# 1-Schematic_New_Project.net
KiCad netlist of a schematic drawn in EasyEDA
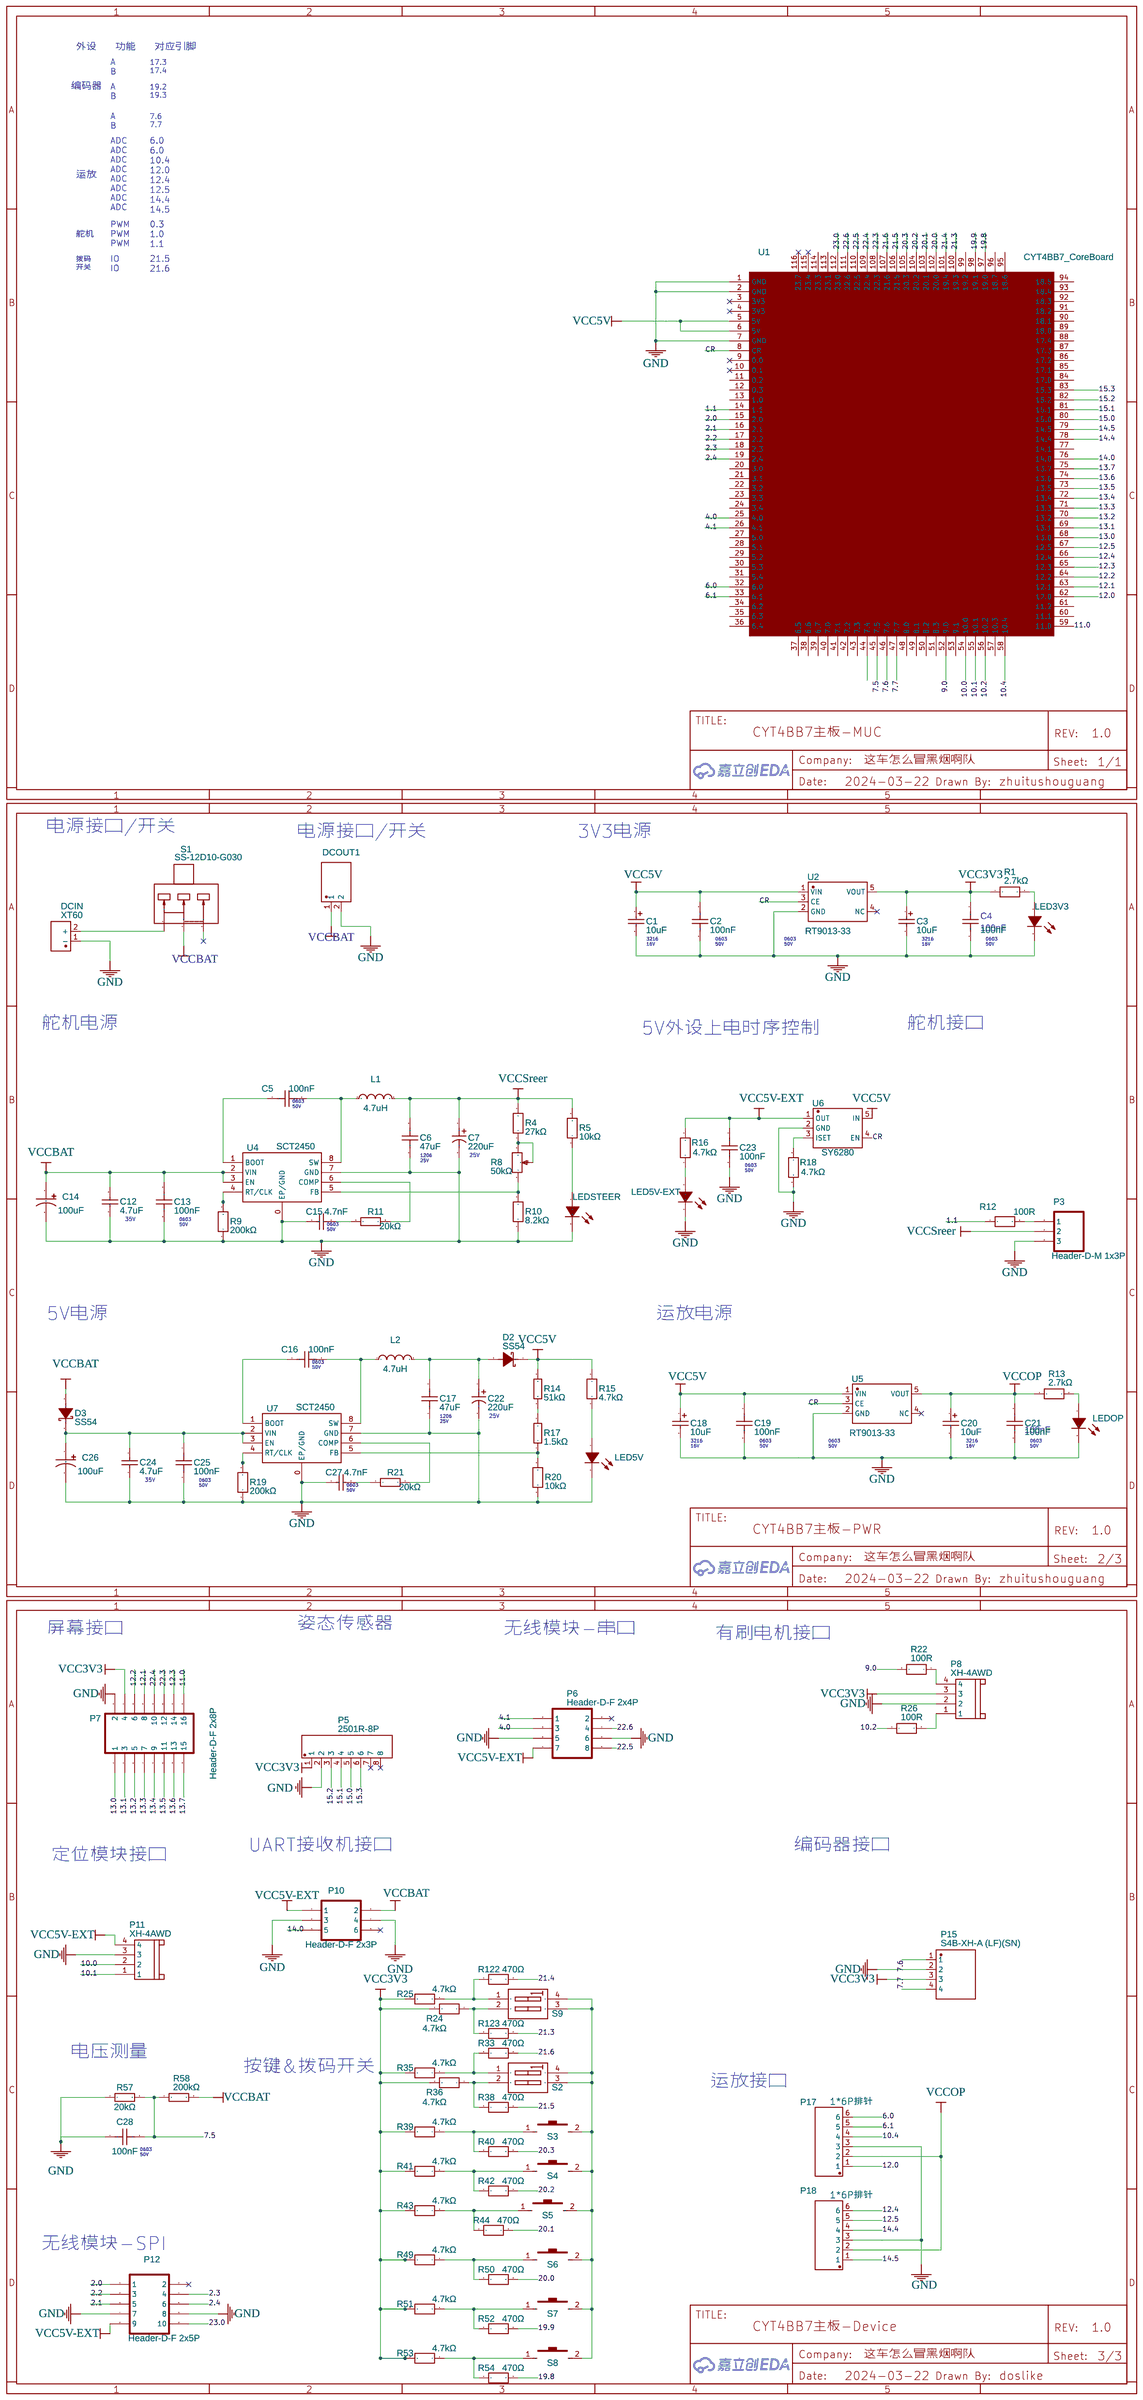
[diagram p0: schematic sheet]

(export (version "E")
  (design (tool "Eeschema 10.0.6"))
  (components
    (comp (ref "C1")
      (value "10uF")
      (fields
        (field (name "Manufacturer Part") "CA45A-A-16V-10uF-K")
        (field (name "Manufacturer") "CEC(振华新云)")
      )
      (libsource (lib "") (part "CA45A-A-16V-10UF-K"))
    )
    (comp (ref "C2")
      (value "100nF")
      (fields (field (name "Manufacturer Part") "100nF/0603/50V"))
      (libsource (lib "") (part "100NF/0603/50V"))
    )
    (comp (ref "C3")
      (value "10uF")
      (fields
        (field (name "Manufacturer Part") "CA45A-A-16V-10uF-K")
        (field (name "Manufacturer") "CEC(振华新云)")
      )
      (libsource (lib "") (part "CA45A-A-16V-10UF-K"))
    )
    (comp (ref "C4")
      (value "100nF")
      (fields (field (name "Manufacturer Part") "100nF/0603/50V"))
      (libsource (lib "") (part "100NF/0603/50V"))
    )
    (comp (ref "C5")
      (value "100nF")
      (fields (field (name "Manufacturer Part") "100nF/0603/50V"))
      (libsource (lib "") (part "100NF/0603/50V_1"))
    )
    (comp (ref "C6")
      (value "47uF")
      (fields (field (name "Manufacturer Part") "47uF, 25V,10%-1206"))
      (libsource (lib "") (part "47UF, 25V,10%-1206"))
    )
    (comp (ref "C7")
      (value "220uF")
      (fields
        (field (name "Manufacturer Part") "KNE2220UF25V149EC0030")
        (field (name "Manufacturer") "KNSCHA(科尼盛)")
      )
      (libsource (lib "") (part "KNE2220UF25V149EC0030"))
    )
    (comp (ref "C12")
      (value "4.7uF")
      (fields (field (name "Manufacturer Part") "12065C475KAT2A") (field (name "Manufacturer") "Kyocera AVX"))
      (libsource (lib "") (part "12065C475KAT4A"))
    )
    (comp (ref "C13")
      (value "100nF")
      (fields (field (name "Manufacturer Part") "100nF/0603/50V"))
      (libsource (lib "") (part "100NF/0603/50V"))
    )
    (comp (ref "C14")
      (value "100uF")
      (fields
        (field (name "Manufacturer Part") "16NA100MEFC6.3X11")
        (field (name "Manufacturer") "rubycon(红宝石)")
      )
      (libsource (lib "") (part "16NA100MEFC6.3X11"))
    )
    (comp (ref "C15")
      (value "4.7nF")
      (fields (field (name "Manufacturer Part") "C0603N472J050T") (field (name "Manufacturer") "HEC(禾伸堂)"))
      (libsource (lib "") (part "0603-4.7nF-50V-10%-NPO"))
    )
    (comp (ref "C16")
      (value "100nF")
      (fields (field (name "Manufacturer Part") "100nF/0603/50V"))
      (libsource (lib "") (part "100NF/0603/50V_1"))
    )
    (comp (ref "C17")
      (value "47uF")
      (fields (field (name "Manufacturer Part") "47uF, 25V,10%-1206"))
      (libsource (lib "") (part "47UF, 25V,10%-1206"))
    )
    (comp (ref "C18")
      (value "10uF")
      (fields
        (field (name "Manufacturer Part") "CA45A-A-16V-10uF-K")
        (field (name "Manufacturer") "CEC(振华新云)")
      )
      (libsource (lib "") (part "CA45A-A-16V-10UF-K"))
    )
    (comp (ref "C19")
      (value "100nF")
      (fields (field (name "Manufacturer Part") "100nF/0603/50V"))
      (libsource (lib "") (part "100NF/0603/50V"))
    )
    (comp (ref "C20")
      (value "10uF")
      (fields
        (field (name "Manufacturer Part") "CA45A-A-16V-10uF-K")
        (field (name "Manufacturer") "CEC(振华新云)")
      )
      (libsource (lib "") (part "CA45A-A-16V-10UF-K"))
    )
    (comp (ref "C21")
      (value "100nF")
      (fields (field (name "Manufacturer Part") "100nF/0603/50V"))
      (libsource (lib "") (part "100NF/0603/50V"))
    )
    (comp (ref "C22")
      (value "220uF")
      (fields
        (field (name "Manufacturer Part") "KNE2220UF25V149EC0030")
        (field (name "Manufacturer") "KNSCHA(科尼盛)")
      )
      (libsource (lib "") (part "KNE2220UF25V149EC0030"))
    )
    (comp (ref "C23")
      (value "100nF")
      (fields (field (name "Manufacturer Part") "100nF/0603/50V"))
      (libsource (lib "") (part "100NF/0603/50V"))
    )
    (comp (ref "C24")
      (value "4.7uF")
      (fields (field (name "Manufacturer Part") "12065C475KAT2A") (field (name "Manufacturer") "Kyocera AVX"))
      (libsource (lib "") (part "12065C475KAT4A"))
    )
    (comp (ref "C25")
      (value "100nF")
      (fields (field (name "Manufacturer Part") "100nF/0603/50V"))
      (libsource (lib "") (part "100NF/0603/50V"))
    )
    (comp (ref "C26")
      (value "100uF")
      (fields
        (field (name "Manufacturer Part") "16NA100MEFC6.3X11")
        (field (name "Manufacturer") "rubycon(红宝石)")
      )
      (libsource (lib "") (part "16NA100MEFC6.3X11"))
    )
    (comp (ref "C27")
      (value "4.7nF")
      (fields (field (name "Manufacturer Part") "C0603N472J050T") (field (name "Manufacturer") "HEC(禾伸堂)"))
      (libsource (lib "") (part "0603-4.7nF-50V-10%-NPO"))
    )
    (comp (ref "C28")
      (value "100nF")
      (fields (field (name "Manufacturer Part") "100nF/0603/50V"))
      (libsource (lib "") (part "100NF/0603/50V_1"))
    )
    (comp (ref "D2")
      (value "SS54")
      (fields (field (name "Manufacturer") "Zhengxin(正芯)"))
      (libsource (lib "") (part "SS54_1"))
    )
    (comp (ref "D3")
      (value "SS54")
      (fields (field (name "Manufacturer") "Zhengxin(正芯)"))
      (libsource (lib "") (part "SS54"))
    )
    (comp (ref "DCIN")
      (value "XT60")
      (fields (field (name "Manufacturer") "AMASS(艾迈斯)"))
      (libsource (lib "") (part "XT60"))
    )
    (comp (ref "DCOUT1")
      (value "DCOUT")
      (fields (field (name "Manufacturer Part") "EK500V-02P") (field (name "Manufacturer") "dinkle(町洋)"))
      (libsource (lib "") (part "EK500V-02P"))
    )
    (comp (ref "L1")
      (value "4.7uH")
      (fields
        (field (name "Manufacturer Part") "CKCS4020-4.7uH/M")
        (field (name "Manufacturer") "CENKER(岑科)")
      )
      (libsource (lib "") (part "CKCS4020-4.7UH/M"))
    )
    (comp (ref "L2")
      (value "4.7uH")
      (fields
        (field (name "Manufacturer Part") "CKCS4020-4.7uH/M")
        (field (name "Manufacturer") "CENKER(岑科)")
      )
      (libsource (lib "") (part "CKCS4020-4.7UH/M"))
    )
    (comp (ref "LED3V3")
      (value "91-21SURC/S530-A2/TR10")
      (fields (field (name "Manufacturer") "EVERLIGHT(亿光)"))
      (libsource (lib "") (part "91-21SURC/S530-A2/TR10_4"))
    )
    (comp (ref "LED5V")
      (value "91-21SURC/S530-A2/TR10")
      (fields (field (name "Manufacturer") "EVERLIGHT(亿光)"))
      (libsource (lib "") (part "91-21SURC/S530-A2/TR10_2"))
    )
    (comp (ref "LED5V-EXT")
      (value "91-21SURC/S530-A2/TR10")
      (fields (field (name "Manufacturer") "EVERLIGHT(亿光)"))
      (libsource (lib "") (part "91-21SURC/S530-A2/TR10_3"))
    )
    (comp (ref "LEDOP")
      (value "91-21SURC/S530-A2/TR10")
      (fields (field (name "Manufacturer") "EVERLIGHT(亿光)"))
      (libsource (lib "") (part "91-21SURC/S530-A2/TR10"))
    )
    (comp (ref "LEDSTEER")
      (value "91-21SURC/S530-A2/TR10")
      (fields (field (name "Manufacturer") "EVERLIGHT(亿光)"))
      (libsource (lib "") (part "91-21SURC/S530-A2/TR10_1"))
    )
    (comp (ref "P3") (value "Header-D-M 1x3P") (libsource (lib "") (part "Header-D-M 1x3P")))
    (comp (ref "P5")
      (value "2501R-8P")
      (fields (field (name "Manufacturer Part") "W-2501R08P-N000") (field (name "Manufacturer") "Ckmtw(灿科盟)"))
      (libsource (lib "") (part "2501R-8P"))
    )
    (comp (ref "P6") (value "Header-D-F 2x4P") (libsource (lib "") (part "Header-D-F 2x4P")))
    (comp (ref "P7") (value "Header-D-F 2x8P") (libsource (lib "") (part "Header-D-F 2x8P")))
    (comp (ref "P8")
      (value "XH-4AWD")
      (fields (field (name "Manufacturer") "BOOMELE(博穆精密)"))
      (libsource (lib "") (part "XH-4AWD"))
    )
    (comp (ref "P10") (value "Header-D-F 2x3P") (libsource (lib "") (part "Header-D-F 2x3P")))
    (comp (ref "P11")
      (value "XH-4AWD")
      (fields (field (name "Manufacturer") "BOOMELE(博穆精密)"))
      (libsource (lib "") (part "XH-4AWD"))
    )
    (comp (ref "P12") (value "Header-D-F 2x5P") (libsource (lib "") (part "Header-D-F 2x5P")))
    (comp (ref "P15")
      (value "S4B-XH-A (LF)(SN)")
      (fields (field (name "Manufacturer Part") "S4B-XH-A(LF)(SN)") (field (name "Manufacturer") "JST"))
      (libsource (lib "") (part "S4B-XH-A (LF)(SN)"))
    )
    (comp (ref "P17")
      (value "1*6P排针")
      (fields
        (field (name "Manufacturer Part") "2.54mm 1*40P Reverse bending Headers  Pins")
        (field (name "Manufacturer") "BOOMELE")
      )
      (libsource (lib "") (part "2.54mm 1*6P排针"))
    )
    (comp (ref "P18")
      (value "1*6P排针")
      (fields
        (field (name "Manufacturer Part") "2.54mm 1*40P Reverse bending Headers  Pins")
        (field (name "Manufacturer") "BOOMELE")
      )
      (libsource (lib "") (part "2.54mm 1*6P排针"))
    )
    (comp (ref "R1")
      (value "2.7kΩ")
      (fields (field (name "Manufacturer Part") "FRC2010F2701TS") (field (name "Manufacturer") "FOJAN(富捷)"))
      (libsource (lib "") (part "FRC2010F2701TS"))
    )
    (comp (ref "R4")
      (value "27kΩ")
      (fields
        (field (name "Manufacturer Part") "MMA02040E2702BB300")
        (field (name "Manufacturer") "VISHAY(威世)")
      )
      (libsource (lib "") (part "MMA02040E2702BB300"))
    )
    (comp (ref "R5")
      (value "10kΩ")
      (fields (field (name "Manufacturer Part") "AR05DTD1002") (field (name "Manufacturer") "Viking(光颉)"))
      (libsource (lib "") (part "AR05DTD1002"))
    )
    (comp (ref "R8")
      (value "50kΩ")
      (fields (field (name "Manufacturer Part") "3296W-1-503-8mm") (field (name "Manufacturer") "BOCHEN(博晨)"))
      (libsource (lib "") (part "3296W-1-503_C330434"))
    )
    (comp (ref "R9")
      (value "200kΩ")
      (fields (field (name "Manufacturer Part") "FRC1812J204 TS") (field (name "Manufacturer") "FOJAN(富捷)"))
      (libsource (lib "") (part "FRC1812J204 TS"))
    )
    (comp (ref "R10")
      (value "8.2kΩ")
      (fields
        (field (name "Manufacturer Part") "0201WMJ0822TEE")
        (field (name "Manufacturer") "UNI-ROYAL(厚声)")
      )
      (libsource (lib "") (part "0201WMJ0822TEE"))
    )
    (comp (ref "R11")
      (value "20kΩ")
      (fields (field (name "Manufacturer Part") "SG73S1JTTD203J") (field (name "Manufacturer") "KOA"))
      (libsource (lib "") (part "SG73S1JTTD203J"))
    )
    (comp (ref "R12")
      (value "100R")
      (fields (field (name "Manufacturer Part") "AC0402DR-07100RL") (field (name "Manufacturer") "YAGEO(国巨)"))
      (libsource (lib "") (part "AC0402DR-07100RL"))
    )
    (comp (ref "R13")
      (value "2.7kΩ")
      (fields (field (name "Manufacturer Part") "FRC2010F2701TS") (field (name "Manufacturer") "FOJAN(富捷)"))
      (libsource (lib "") (part "FRC2010F2701TS"))
    )
    (comp (ref "R14")
      (value "51kΩ")
      (fields
        (field (name "Manufacturer Part") "0805W8F5102T5E")
        (field (name "Manufacturer") "UNI-ROYAL(厚声)")
      )
      (libsource (lib "") (part "0805W8F5102T5E"))
    )
    (comp (ref "R15")
      (value "4.7kΩ")
      (fields (field (name "Manufacturer Part") "1206 ±5% 4K7") (field (name "Manufacturer") "VO(翔胜)"))
      (libsource (lib "") (part "1206 ±5% 4K7_1"))
    )
    (comp (ref "R16")
      (value "4.7kΩ")
      (fields (field (name "Manufacturer Part") "1206 ±5% 4K7") (field (name "Manufacturer") "VO(翔胜)"))
      (libsource (lib "") (part "1206 ±5% 4K7_1"))
    )
    (comp (ref "R17")
      (value "1.5kΩ")
      (fields
        (field (name "Manufacturer Part") "0402WGF1501TCE")
        (field (name "Manufacturer") "UNI-ROYAL(厚声)")
      )
      (libsource (lib "") (part "0402WGF1501TCE"))
    )
    (comp (ref "R18")
      (value "4.7kΩ")
      (fields (field (name "Manufacturer Part") "1206 ±5% 4K7") (field (name "Manufacturer") "VO(翔胜)"))
      (libsource (lib "") (part "1206 ±5% 4K7_1"))
    )
    (comp (ref "R19")
      (value "200kΩ")
      (fields (field (name "Manufacturer Part") "FRC1812J204 TS") (field (name "Manufacturer") "FOJAN(富捷)"))
      (libsource (lib "") (part "FRC1812J204 TS"))
    )
    (comp (ref "R20")
      (value "10kΩ")
      (fields (field (name "Manufacturer Part") "AR03BTD1002") (field (name "Manufacturer") "Viking(光颉)"))
      (libsource (lib "") (part "AR03BTD1002"))
    )
    (comp (ref "R21")
      (value "20kΩ")
      (fields (field (name "Manufacturer Part") "SG73S1JTTD203J") (field (name "Manufacturer") "KOA"))
      (libsource (lib "") (part "SG73S1JTTD203J"))
    )
    (comp (ref "R22")
      (value "100R")
      (fields (field (name "Manufacturer Part") "AC0402DR-07100RL") (field (name "Manufacturer") "YAGEO(国巨)"))
      (libsource (lib "") (part "AC0402DR-07100RL_1"))
    )
    (comp (ref "R24")
      (value "4.7kΩ")
      (fields (field (name "Manufacturer Part") "1206 ±5% 4K7") (field (name "Manufacturer") "VO(翔胜)"))
      (libsource (lib "") (part "1206 ±5% 4K7"))
    )
    (comp (ref "R25")
      (value "4.7kΩ")
      (fields (field (name "Manufacturer Part") "1206 ±5% 4K7") (field (name "Manufacturer") "VO(翔胜)"))
      (libsource (lib "") (part "1206 ±5% 4K7"))
    )
    (comp (ref "R26")
      (value "100R")
      (fields (field (name "Manufacturer Part") "AC0402DR-07100RL") (field (name "Manufacturer") "YAGEO(国巨)"))
      (libsource (lib "") (part "AC0402DR-07100RL"))
    )
    (comp (ref "R33")
      (value "470Ω")
      (fields (field (name "Manufacturer Part") "SCR1206F470R") (field (name "Manufacturer") "VO(翔胜)"))
      (libsource (lib "") (part "SCR1206F470R"))
    )
    (comp (ref "R35")
      (value "4.7kΩ")
      (fields (field (name "Manufacturer Part") "1206 ±5% 4K7") (field (name "Manufacturer") "VO(翔胜)"))
      (libsource (lib "") (part "1206 ±5% 4K7"))
    )
    (comp (ref "R36")
      (value "4.7kΩ")
      (fields (field (name "Manufacturer Part") "1206 ±5% 4K7") (field (name "Manufacturer") "VO(翔胜)"))
      (libsource (lib "") (part "1206 ±5% 4K7"))
    )
    (comp (ref "R38")
      (value "470Ω")
      (fields (field (name "Manufacturer Part") "SCR1206F470R") (field (name "Manufacturer") "VO(翔胜)"))
      (libsource (lib "") (part "SCR1206F470R"))
    )
    (comp (ref "R39")
      (value "4.7kΩ")
      (fields (field (name "Manufacturer Part") "1206 ±5% 4K7") (field (name "Manufacturer") "VO(翔胜)"))
      (libsource (lib "") (part "1206 ±5% 4K7"))
    )
    (comp (ref "R40")
      (value "470Ω")
      (fields (field (name "Manufacturer Part") "SCR1206F470R") (field (name "Manufacturer") "VO(翔胜)"))
      (libsource (lib "") (part "SCR1206F470R"))
    )
    (comp (ref "R41")
      (value "4.7kΩ")
      (fields (field (name "Manufacturer Part") "1206 ±5% 4K7") (field (name "Manufacturer") "VO(翔胜)"))
      (libsource (lib "") (part "1206 ±5% 4K7"))
    )
    (comp (ref "R42")
      (value "470Ω")
      (fields (field (name "Manufacturer Part") "SCR1206F470R") (field (name "Manufacturer") "VO(翔胜)"))
      (libsource (lib "") (part "SCR1206F470R"))
    )
    (comp (ref "R43")
      (value "4.7kΩ")
      (fields (field (name "Manufacturer Part") "1206 ±5% 4K7") (field (name "Manufacturer") "VO(翔胜)"))
      (libsource (lib "") (part "1206 ±5% 4K7"))
    )
    (comp (ref "R44")
      (value "470Ω")
      (fields (field (name "Manufacturer Part") "SCR1206F470R") (field (name "Manufacturer") "VO(翔胜)"))
      (libsource (lib "") (part "SCR1206F470R"))
    )
    (comp (ref "R49")
      (value "4.7kΩ")
      (fields (field (name "Manufacturer Part") "1206 ±5% 4K7") (field (name "Manufacturer") "VO(翔胜)"))
      (libsource (lib "") (part "1206 ±5% 4K7"))
    )
    (comp (ref "R50")
      (value "470Ω")
      (fields (field (name "Manufacturer Part") "SCR1206F470R") (field (name "Manufacturer") "VO(翔胜)"))
      (libsource (lib "") (part "SCR1206F470R"))
    )
    (comp (ref "R51")
      (value "4.7kΩ")
      (fields (field (name "Manufacturer Part") "1206 ±5% 4K7") (field (name "Manufacturer") "VO(翔胜)"))
      (libsource (lib "") (part "1206 ±5% 4K7"))
    )
    (comp (ref "R52")
      (value "470Ω")
      (fields (field (name "Manufacturer Part") "SCR1206F470R") (field (name "Manufacturer") "VO(翔胜)"))
      (libsource (lib "") (part "SCR1206F470R"))
    )
    (comp (ref "R53")
      (value "4.7kΩ")
      (fields (field (name "Manufacturer Part") "1206 ±5% 4K7") (field (name "Manufacturer") "VO(翔胜)"))
      (libsource (lib "") (part "1206 ±5% 4K7"))
    )
    (comp (ref "R54")
      (value "470Ω")
      (fields (field (name "Manufacturer Part") "SCR1206F470R") (field (name "Manufacturer") "VO(翔胜)"))
      (libsource (lib "") (part "SCR1206F470R"))
    )
    (comp (ref "R57")
      (value "20kΩ")
      (fields (field (name "Manufacturer Part") "WR08X203JTL") (field (name "Manufacturer") "Walsin(华新科)"))
      (libsource (lib "") (part "WR08X203JTL"))
    )
    (comp (ref "R58")
      (value "200kΩ")
      (fields (field (name "Manufacturer Part") "WR12X204JTL") (field (name "Manufacturer") "Walsin(华新科)"))
      (libsource (lib "") (part "WR12X204JTL"))
    )
    (comp (ref "R122")
      (value "470Ω")
      (fields (field (name "Manufacturer Part") "SCR1206F470R") (field (name "Manufacturer") "VO(翔胜)"))
      (libsource (lib "") (part "SCR1206F470R"))
    )
    (comp (ref "R123")
      (value "470Ω")
      (fields (field (name "Manufacturer Part") "SCR1206F470R") (field (name "Manufacturer") "VO(翔胜)"))
      (libsource (lib "") (part "SCR1206F470R"))
    )
    (comp (ref "S1")
      (value "SS-12D10-G030")
      (fields (field (name "Manufacturer") "G-Switch(品赞)"))
      (libsource (lib "") (part "SS-12D10-G030"))
    )
    (comp (ref "S2")
      (value "CDH-02")
      (fields (field (name "Manufacturer") "Cha(昭华)"))
      (libsource (lib "") (part "CDH-02"))
    )
    (comp (ref "S3")
      (value "8:5h Camera switch")
      (fields (field (name "Manufacturer Part") "8:5h 相机开关"))
      (libsource (lib "") (part "8{colon}5h Camera switch"))
    )
    (comp (ref "S4")
      (value "8:5h Camera switch")
      (fields (field (name "Manufacturer Part") "8:5h 相机开关"))
      (libsource (lib "") (part "8{colon}5h Camera switch"))
    )
    (comp (ref "S5")
      (value "8:5h Camera switch")
      (fields (field (name "Manufacturer Part") "8:5h 相机开关"))
      (libsource (lib "") (part "8{colon}5h Camera switch"))
    )
    (comp (ref "S6")
      (value "8:5h Camera switch")
      (fields (field (name "Manufacturer Part") "8:5h 相机开关"))
      (libsource (lib "") (part "8{colon}5h Camera switch"))
    )
    (comp (ref "S7")
      (value "8:5h Camera switch")
      (fields (field (name "Manufacturer Part") "8:5h 相机开关"))
      (libsource (lib "") (part "8{colon}5h Camera switch"))
    )
    (comp (ref "S8")
      (value "8:5h Camera switch")
      (fields (field (name "Manufacturer Part") "8:5h 相机开关"))
      (libsource (lib "") (part "8{colon}5h Camera switch"))
    )
    (comp (ref "S9")
      (value "CDH-02")
      (fields (field (name "Manufacturer") "Cha(昭华)"))
      (libsource (lib "") (part "CDH-02"))
    )
    (comp (ref "U1") (value "CYT4BB7_CoreBoard") (libsource (lib "") (part "CYT4BB7CEx_CoreBoard")))
    (comp (ref "U2")
      (value "RT9013-33")
      (fields
        (field (name "Manufacturer Part") "RT9013-33GB")
        (field (name "Manufacturer") "TECH PUBLIC(台舟)")
      )
      (libsource (lib "") (part "RT9013-33GB_C19268157"))
    )
    (comp (ref "U4") (value "SCT2450") (libsource (lib "") (part "SCT2450")))
    (comp (ref "U5")
      (value "RT9013-33")
      (fields
        (field (name "Manufacturer Part") "RT9013-33GB")
        (field (name "Manufacturer") "TECH PUBLIC(台舟)")
      )
      (libsource (lib "") (part "RT9013-33GB_C19268157"))
    )
    (comp (ref "U6")
      (value "SY6280")
      (fields (field (name "Manufacturer Part") "SY6280AAC") (field (name "Manufacturer") "silergy(矽力杰)"))
      (libsource (lib "") (part "SY6280AAC"))
    )
    (comp (ref "U7") (value "SCT2450") (libsource (lib "") (part "SCT2450")))
  )
  (nets
    (net (code "1") (name "/1.1") (class "Default")
      (node (ref "R12") (pin "1") (pinfunction "1_1") (pintype "unspecified"))
      (node (ref "U1") (pin "14") (pinfunction "1.1_14") (pintype "unspecified"))
    )
    (net (code "2") (name "/2.0") (class "Default")
      (node (ref "P12") (pin "1") (pinfunction "1_1") (pintype "unspecified"))
      (node (ref "U1") (pin "15") (pinfunction "2.0_15") (pintype "unspecified"))
    )
    (net (code "3") (name "/2.1") (class "Default")
      (node (ref "P12") (pin "5") (pinfunction "5_5") (pintype "unspecified"))
      (node (ref "U1") (pin "16") (pinfunction "2.1_16") (pintype "unspecified"))
    )
    (net (code "4") (name "/2.2") (class "Default")
      (node (ref "P12") (pin "3") (pinfunction "3_3") (pintype "unspecified"))
      (node (ref "U1") (pin "17") (pinfunction "2.2_17") (pintype "unspecified"))
    )
    (net (code "5") (name "/2.3") (class "Default")
      (node (ref "P12") (pin "4") (pinfunction "4_4") (pintype "unspecified"))
      (node (ref "U1") (pin "18") (pinfunction "2.3_18") (pintype "unspecified"))
    )
    (net (code "6") (name "/2.4") (class "Default")
      (node (ref "P12") (pin "6") (pinfunction "6_6") (pintype "unspecified"))
      (node (ref "U1") (pin "19") (pinfunction "2.4_19") (pintype "unspecified"))
    )
    (net (code "7") (name "/4.0") (class "Default")
      (node (ref "P6") (pin "3") (pinfunction "3_3") (pintype "unspecified"))
      (node (ref "U1") (pin "25") (pinfunction "4.0_25") (pintype "unspecified"))
    )
    (net (code "8") (name "/4.1") (class "Default")
      (node (ref "P6") (pin "1") (pinfunction "1_1") (pintype "unspecified"))
      (node (ref "U1") (pin "26") (pinfunction "4.1_26") (pintype "unspecified"))
    )
    (net (code "9") (name "/6.0") (class "Default")
      (node (ref "P17") (pin "6") (pinfunction "6_6") (pintype "unspecified"))
      (node (ref "U1") (pin "32") (pinfunction "6.0_32") (pintype "unspecified"))
    )
    (net (code "10") (name "/6.1") (class "Default")
      (node (ref "P17") (pin "5") (pinfunction "5_5") (pintype "unspecified"))
      (node (ref "U1") (pin "33") (pinfunction "6.1_33") (pintype "unspecified"))
    )
    (net (code "11") (name "/7.5") (class "Default")
      (node (ref "C28") (pin "2") (pinfunction "2_2") (pintype "unspecified"))
      (node (ref "R57") (pin "2") (pinfunction "2_2") (pintype "unspecified"))
      (node (ref "R58") (pin "1") (pinfunction "1_1") (pintype "unspecified"))
      (node (ref "U1") (pin "45") (pinfunction "7.5_45") (pintype "unspecified"))
    )
    (net (code "12") (name "/7.6") (class "Default")
      (node (ref "P15") (pin "1") (pinfunction "1_1") (pintype "unspecified"))
      (node (ref "U1") (pin "46") (pinfunction "7.6_46") (pintype "unspecified"))
    )
    (net (code "13") (name "/7.7") (class "Default")
      (node (ref "P15") (pin "4") (pinfunction "4_4") (pintype "unspecified"))
      (node (ref "U1") (pin "47") (pinfunction "7.7_47") (pintype "unspecified"))
    )
    (net (code "14") (name "/9.0") (class "Default")
      (node (ref "R22") (pin "2") (pinfunction "2_2") (pintype "unspecified"))
      (node (ref "U1") (pin "52") (pinfunction "9.0_52") (pintype "unspecified"))
    )
    (net (code "15") (name "/10.0") (class "Default")
      (node (ref "P11") (pin "2") (pinfunction "2_2") (pintype "unspecified"))
      (node (ref "U1") (pin "54") (pinfunction "10.0_54") (pintype "unspecified"))
    )
    (net (code "16") (name "/10.1") (class "Default")
      (node (ref "P11") (pin "1") (pinfunction "1_1") (pintype "unspecified"))
      (node (ref "U1") (pin "55") (pinfunction "10.1_55") (pintype "unspecified"))
    )
    (net (code "17") (name "/10.2") (class "Default")
      (node (ref "R26") (pin "1") (pinfunction "1_1") (pintype "unspecified"))
      (node (ref "U1") (pin "56") (pinfunction "10.2_56") (pintype "unspecified"))
    )
    (net (code "18") (name "/10.4") (class "Default")
      (node (ref "P17") (pin "4") (pinfunction "4_4") (pintype "unspecified"))
      (node (ref "U1") (pin "58") (pinfunction "10.4_58") (pintype "unspecified"))
    )
    (net (code "19") (name "/11.0") (class "Default")
      (node (ref "P7") (pin "16") (pinfunction "16_16") (pintype "unspecified"))
      (node (ref "U1") (pin "59") (pinfunction "11.0_59") (pintype "unspecified"))
    )
    (net (code "20") (name "/12.0") (class "Default")
      (node (ref "P17") (pin "1") (pinfunction "1_1") (pintype "unspecified"))
      (node (ref "U1") (pin "62") (pinfunction "12.0_62") (pintype "unspecified"))
    )
    (net (code "21") (name "/12.1") (class "Default")
      (node (ref "P7") (pin "8") (pinfunction "8_8") (pintype "unspecified"))
      (node (ref "U1") (pin "63") (pinfunction "12.1_63") (pintype "unspecified"))
    )
    (net (code "22") (name "/12.2") (class "Default")
      (node (ref "P7") (pin "6") (pinfunction "6_6") (pintype "unspecified"))
      (node (ref "U1") (pin "64") (pinfunction "12.2_64") (pintype "unspecified"))
    )
    (net (code "23") (name "/12.3") (class "Default")
      (node (ref "P7") (pin "14") (pinfunction "14_14") (pintype "unspecified"))
      (node (ref "U1") (pin "65") (pinfunction "12.3_65") (pintype "unspecified"))
    )
    (net (code "24") (name "/12.4") (class "Default")
      (node (ref "P18") (pin "6") (pinfunction "6_6") (pintype "unspecified"))
      (node (ref "U1") (pin "66") (pinfunction "12.4_66") (pintype "unspecified"))
    )
    (net (code "25") (name "/12.5") (class "Default")
      (node (ref "P18") (pin "5") (pinfunction "5_5") (pintype "unspecified"))
      (node (ref "U1") (pin "67") (pinfunction "12.5_67") (pintype "unspecified"))
    )
    (net (code "26") (name "/13.0") (class "Default")
      (node (ref "P7") (pin "1") (pinfunction "1_1") (pintype "unspecified"))
      (node (ref "U1") (pin "68") (pinfunction "13.0_68") (pintype "unspecified"))
    )
    (net (code "27") (name "/13.1") (class "Default")
      (node (ref "P7") (pin "3") (pinfunction "3_3") (pintype "unspecified"))
      (node (ref "U1") (pin "69") (pinfunction "13.1_69") (pintype "unspecified"))
    )
    (net (code "28") (name "/13.2") (class "Default")
      (node (ref "P7") (pin "5") (pinfunction "5_5") (pintype "unspecified"))
      (node (ref "U1") (pin "70") (pinfunction "13.2_70") (pintype "unspecified"))
    )
    (net (code "29") (name "/13.3") (class "Default")
      (node (ref "P7") (pin "7") (pinfunction "7_7") (pintype "unspecified"))
      (node (ref "U1") (pin "71") (pinfunction "13.3_71") (pintype "unspecified"))
    )
    (net (code "30") (name "/13.4") (class "Default")
      (node (ref "P7") (pin "9") (pinfunction "9_9") (pintype "unspecified"))
      (node (ref "U1") (pin "72") (pinfunction "13.4_72") (pintype "unspecified"))
    )
    (net (code "31") (name "/13.5") (class "Default")
      (node (ref "P7") (pin "11") (pinfunction "11_11") (pintype "unspecified"))
      (node (ref "U1") (pin "73") (pinfunction "13.5_73") (pintype "unspecified"))
    )
    (net (code "32") (name "/13.6") (class "Default")
      (node (ref "P7") (pin "13") (pinfunction "13_13") (pintype "unspecified"))
      (node (ref "U1") (pin "74") (pinfunction "13.6_74") (pintype "unspecified"))
    )
    (net (code "33") (name "/13.7") (class "Default")
      (node (ref "P7") (pin "15") (pinfunction "15_15") (pintype "unspecified"))
      (node (ref "U1") (pin "75") (pinfunction "13.7_75") (pintype "unspecified"))
    )
    (net (code "34") (name "/14.0") (class "Default")
      (node (ref "P10") (pin "5") (pinfunction "5_5") (pintype "unspecified"))
      (node (ref "U1") (pin "76") (pinfunction "14.0_76") (pintype "unspecified"))
    )
    (net (code "35") (name "/14.4") (class "Default")
      (node (ref "P18") (pin "4") (pinfunction "4_4") (pintype "unspecified"))
      (node (ref "U1") (pin "78") (pinfunction "14.4_78") (pintype "unspecified"))
    )
    (net (code "36") (name "/14.5") (class "Default")
      (node (ref "P18") (pin "1") (pinfunction "1_1") (pintype "unspecified"))
      (node (ref "U1") (pin "79") (pinfunction "14.5_79") (pintype "unspecified"))
    )
    (net (code "37") (name "/15.0") (class "Default")
      (node (ref "P5") (pin "5") (pinfunction "5_5") (pintype "unspecified"))
      (node (ref "U1") (pin "80") (pinfunction "15.0_80") (pintype "unspecified"))
    )
    (net (code "38") (name "/15.1") (class "Default")
      (node (ref "P5") (pin "4") (pinfunction "4_4") (pintype "unspecified"))
      (node (ref "U1") (pin "81") (pinfunction "15.1_81") (pintype "unspecified"))
    )
    (net (code "39") (name "/15.2") (class "Default")
      (node (ref "P5") (pin "3") (pinfunction "3_3") (pintype "unspecified"))
      (node (ref "U1") (pin "82") (pinfunction "15.2_82") (pintype "unspecified"))
    )
    (net (code "40") (name "/15.3") (class "Default")
      (node (ref "P5") (pin "6") (pinfunction "6_6") (pintype "unspecified"))
      (node (ref "U1") (pin "83") (pinfunction "15.3_83") (pintype "unspecified"))
    )
    (net (code "41") (name "/19.8") (class "Default")
      (node (ref "R54") (pin "2") (pinfunction "2_2") (pintype "unspecified"))
      (node (ref "U1") (pin "97") (pinfunction "19.0_97") (pintype "unspecified"))
    )
    (net (code "42") (name "/19.9") (class "Default")
      (node (ref "R52") (pin "2") (pinfunction "2_2") (pintype "unspecified"))
      (node (ref "U1") (pin "98") (pinfunction "19.1_98") (pintype "unspecified"))
    )
    (net (code "43") (name "/20.0") (class "Default")
      (node (ref "R50") (pin "2") (pinfunction "2_2") (pintype "unspecified"))
      (node (ref "U1") (pin "102") (pinfunction "20.0_102") (pintype "unspecified"))
    )
    (net (code "44") (name "/20.1") (class "Default")
      (node (ref "R44") (pin "2") (pinfunction "2_2") (pintype "unspecified"))
      (node (ref "U1") (pin "103") (pinfunction "20.1_103") (pintype "unspecified"))
    )
    (net (code "45") (name "/20.2") (class "Default")
      (node (ref "R42") (pin "2") (pinfunction "2_2") (pintype "unspecified"))
      (node (ref "U1") (pin "104") (pinfunction "20.2_104") (pintype "unspecified"))
    )
    (net (code "46") (name "/20.3") (class "Default")
      (node (ref "R40") (pin "2") (pinfunction "2_2") (pintype "unspecified"))
      (node (ref "U1") (pin "105") (pinfunction "20.3_105") (pintype "unspecified"))
    )
    (net (code "47") (name "/21.3") (class "Default")
      (node (ref "R123") (pin "2") (pinfunction "2_2") (pintype "unspecified"))
      (node (ref "U1") (pin "100") (pinfunction "19.3_100") (pintype "unspecified"))
    )
    (net (code "48") (name "/21.4") (class "Default")
      (node (ref "R122") (pin "2") (pinfunction "2_2") (pintype "unspecified"))
      (node (ref "U1") (pin "101") (pinfunction "19.4_101") (pintype "unspecified"))
    )
    (net (code "49") (name "/21.5") (class "Default")
      (node (ref "R38") (pin "2") (pinfunction "2_2") (pintype "unspecified"))
      (node (ref "U1") (pin "106") (pinfunction "21.5_106") (pintype "unspecified"))
    )
    (net (code "50") (name "/21.6") (class "Default")
      (node (ref "R33") (pin "2") (pinfunction "2_2") (pintype "unspecified"))
      (node (ref "U1") (pin "107") (pinfunction "21.6_107") (pintype "unspecified"))
    )
    (net (code "51") (name "/22.3") (class "Default")
      (node (ref "P7") (pin "12") (pinfunction "12_12") (pintype "unspecified"))
      (node (ref "U1") (pin "108") (pinfunction "22.3_108") (pintype "unspecified"))
    )
    (net (code "52") (name "/22.4") (class "Default")
      (node (ref "P7") (pin "10") (pinfunction "10_10") (pintype "unspecified"))
      (node (ref "U1") (pin "109") (pinfunction "22.4_109") (pintype "unspecified"))
    )
    (net (code "53") (name "/22.5") (class "Default")
      (node (ref "P6") (pin "8") (pinfunction "8_8") (pintype "unspecified"))
      (node (ref "U1") (pin "110") (pinfunction "22.5_110") (pintype "unspecified"))
    )
    (net (code "54") (name "/22.6") (class "Default")
      (node (ref "P6") (pin "4") (pinfunction "4_4") (pintype "unspecified"))
      (node (ref "U1") (pin "111") (pinfunction "22.6_111") (pintype "unspecified"))
    )
    (net (code "55") (name "/23.0") (class "Default")
      (node (ref "P12") (pin "10") (pinfunction "10_10") (pintype "unspecified"))
      (node (ref "U1") (pin "112") (pinfunction "23.0_112") (pintype "unspecified"))
    )
    (net (code "56") (name "/CR") (class "Default")
      (node (ref "U1") (pin "8") (pinfunction "CR_8") (pintype "unspecified"))
      (node (ref "U2") (pin "3") (pinfunction "CE_3") (pintype "unspecified"))
      (node (ref "U5") (pin "3") (pinfunction "CE_3") (pintype "unspecified"))
      (node (ref "U6") (pin "4") (pinfunction "EN_4") (pintype "unspecified"))
    )
    (net (code "57") (name "GND") (class "Default")
      (node (ref "C1") (pin "2") (pinfunction "2_2") (pintype "input"))
      (node (ref "C12") (pin "1") (pinfunction "1_1") (pintype "input"))
      (node (ref "C13") (pin "2") (pinfunction "2_2") (pintype "unspecified"))
      (node (ref "C14") (pin "2") (pinfunction "2_2") (pintype "unspecified"))
      (node (ref "C15") (pin "1") (pinfunction "1_1") (pintype "unspecified"))
      (node (ref "C17") (pin "1") (pinfunction "1_1") (pintype "unspecified"))
      (node (ref "C18") (pin "2") (pinfunction "2_2") (pintype "input"))
      (node (ref "C19") (pin "2") (pinfunction "2_2") (pintype "unspecified"))
      (node (ref "C2") (pin "2") (pinfunction "2_2") (pintype "unspecified"))
      (node (ref "C20") (pin "2") (pinfunction "2_2") (pintype "input"))
      (node (ref "C21") (pin "2") (pinfunction "2_2") (pintype "unspecified"))
      (node (ref "C22") (pin "2") (pinfunction "2_2") (pintype "input"))
      (node (ref "C23") (pin "2") (pinfunction "2_2") (pintype "unspecified"))
      (node (ref "C24") (pin "1") (pinfunction "1_1") (pintype "input"))
      (node (ref "C25") (pin "2") (pinfunction "2_2") (pintype "unspecified"))
      (node (ref "C26") (pin "2") (pinfunction "2_2") (pintype "unspecified"))
      (node (ref "C27") (pin "1") (pinfunction "1_1") (pintype "unspecified"))
      (node (ref "C28") (pin "1") (pinfunction "1_1") (pintype "unspecified"))
      (node (ref "C3") (pin "2") (pinfunction "2_2") (pintype "input"))
      (node (ref "C4") (pin "2") (pinfunction "2_2") (pintype "unspecified"))
      (node (ref "C6") (pin "1") (pinfunction "1_1") (pintype "unspecified"))
      (node (ref "C7") (pin "2") (pinfunction "2_2") (pintype "input"))
      (node (ref "DCIN") (pin "1") (pinfunction "-_1") (pintype "unspecified"))
      (node (ref "DCOUT1") (pin "2") (pinfunction "2_2") (pintype "unspecified"))
      (node (ref "LED3V3") (pin "2") (pinfunction "K_2") (pintype "unspecified"))
      (node (ref "LED5V") (pin "2") (pinfunction "K_2") (pintype "unspecified"))
      (node (ref "LED5V-EXT") (pin "2") (pinfunction "K_2") (pintype "unspecified"))
      (node (ref "LEDOP") (pin "2") (pinfunction "K_2") (pintype "unspecified"))
      (node (ref "LEDSTEER") (pin "2") (pinfunction "K_2") (pintype "unspecified"))
      (node (ref "P10") (pin "3") (pinfunction "3_3") (pintype "unspecified"))
      (node (ref "P10") (pin "4") (pinfunction "4_4") (pintype "unspecified"))
      (node (ref "P11") (pin "3") (pinfunction "3_3") (pintype "unspecified"))
      (node (ref "P12") (pin "7") (pinfunction "7_7") (pintype "unspecified"))
      (node (ref "P12") (pin "8") (pinfunction "8_8") (pintype "unspecified"))
      (node (ref "P15") (pin "2") (pinfunction "2_2") (pintype "unspecified"))
      (node (ref "P17") (pin "3") (pinfunction "3_3") (pintype "unspecified"))
      (node (ref "P18") (pin "3") (pinfunction "3_3") (pintype "unspecified"))
      (node (ref "P3") (pin "3") (pinfunction "3_3") (pintype "unspecified"))
      (node (ref "P5") (pin "2") (pinfunction "2_2") (pintype "unspecified"))
      (node (ref "P6") (pin "5") (pinfunction "5_5") (pintype "unspecified"))
      (node (ref "P6") (pin "6") (pinfunction "6_6") (pintype "unspecified"))
      (node (ref "P7") (pin "2") (pinfunction "2_2") (pintype "unspecified"))
      (node (ref "P8") (pin "2") (pinfunction "2_2") (pintype "unspecified"))
      (node (ref "R10") (pin "1") (pinfunction "1_1") (pintype "unspecified"))
      (node (ref "R18") (pin "1") (pinfunction "1_1") (pintype "unspecified"))
      (node (ref "R19") (pin "1") (pinfunction "1_1") (pintype "unspecified"))
      (node (ref "R20") (pin "1") (pinfunction "1_1") (pintype "unspecified"))
      (node (ref "R57") (pin "1") (pinfunction "1_1") (pintype "unspecified"))
      (node (ref "R9") (pin "1") (pinfunction "1_1") (pintype "unspecified"))
      (node (ref "U1") (pin "1") (pinfunction "GND_1") (pintype "unspecified"))
      (node (ref "U1") (pin "2") (pinfunction "GND_2") (pintype "unspecified"))
      (node (ref "U1") (pin "7") (pinfunction "GND_7") (pintype "unspecified"))
      (node (ref "U2") (pin "2") (pinfunction "GND_2") (pintype "unspecified"))
      (node (ref "U4") (pin "0") (pinfunction "EP/GND_0") (pintype "unspecified"))
      (node (ref "U4") (pin "7") (pinfunction "GND_7") (pintype "unspecified"))
      (node (ref "U5") (pin "2") (pinfunction "GND_2") (pintype "unspecified"))
      (node (ref "U6") (pin "2") (pinfunction "GND_2") (pintype "unspecified"))
      (node (ref "U7") (pin "0") (pinfunction "EP/GND_0") (pintype "unspecified"))
      (node (ref "U7") (pin "7") (pinfunction "GND_7") (pintype "unspecified"))
    )
    (net (code "58") (name "Net-(C15-Pad2)") (class "Default")
      (node (ref "C15") (pin "2") (pinfunction "2_2") (pintype "unspecified"))
      (node (ref "R11") (pin "1") (pinfunction "1_1") (pintype "unspecified"))
    )
    (net (code "59") (name "Net-(C27-Pad2)") (class "Default")
      (node (ref "C27") (pin "2") (pinfunction "2_2") (pintype "unspecified"))
      (node (ref "R21") (pin "1") (pinfunction "1_1") (pintype "unspecified"))
    )
    (net (code "60") (name "Net-(D2-A)") (class "Default")
      (node (ref "C17") (pin "2") (pinfunction "2_2") (pintype "unspecified"))
      (node (ref "C22") (pin "1") (pinfunction "1_1") (pintype "input"))
      (node (ref "D2") (pin "2") (pinfunction "A_2") (pintype "unspecified"))
      (node (ref "L2") (pin "2") (pinfunction "2_2") (pintype "unspecified"))
    )
    (net (code "61") (name "Net-(D3-K)") (class "Default")
      (node (ref "C24") (pin "2") (pinfunction "2_2") (pintype "input"))
      (node (ref "C25") (pin "1") (pinfunction "1_1") (pintype "unspecified"))
      (node (ref "C26") (pin "1") (pinfunction "1_1") (pintype "unspecified"))
      (node (ref "D3") (pin "1") (pinfunction "K_1") (pintype "unspecified"))
      (node (ref "U7") (pin "2") (pinfunction "VIN_2") (pintype "unspecified"))
      (node (ref "U7") (pin "3") (pinfunction "EN_3") (pintype "unspecified"))
    )
    (net (code "62") (name "Net-(DCIN-+)") (class "Default")
      (node (ref "DCIN") (pin "2") (pinfunction "+_2") (pintype "unspecified"))
      (node (ref "S1") (pin "1") (pinfunction "1_1") (pintype "unspecified"))
    )
    (net (code "63") (name "Net-(LED3V3-A)") (class "Default")
      (node (ref "LED3V3") (pin "1") (pinfunction "A_1") (pintype "unspecified"))
      (node (ref "R1") (pin "2") (pinfunction "2_2") (pintype "unspecified"))
    )
    (net (code "64") (name "Net-(LED5V-A)") (class "Default")
      (node (ref "LED5V") (pin "1") (pinfunction "A_1") (pintype "unspecified"))
      (node (ref "R15") (pin "1") (pinfunction "1_1") (pintype "unspecified"))
    )
    (net (code "65") (name "Net-(LED5V-EXT-A)") (class "Default")
      (node (ref "LED5V-EXT") (pin "1") (pinfunction "A_1") (pintype "unspecified"))
      (node (ref "R16") (pin "1") (pinfunction "1_1") (pintype "unspecified"))
    )
    (net (code "66") (name "Net-(LEDOP-A)") (class "Default")
      (node (ref "LEDOP") (pin "1") (pinfunction "A_1") (pintype "unspecified"))
      (node (ref "R13") (pin "2") (pinfunction "2_2") (pintype "unspecified"))
    )
    (net (code "67") (name "Net-(LEDSTEER-A)") (class "Default")
      (node (ref "LEDSTEER") (pin "1") (pinfunction "A_1") (pintype "unspecified"))
      (node (ref "R5") (pin "1") (pinfunction "1_1") (pintype "unspecified"))
    )
    (net (code "68") (name "Net-(P3-Pad1)") (class "Default")
      (node (ref "P3") (pin "1") (pinfunction "1_1") (pintype "unspecified"))
      (node (ref "R12") (pin "2") (pinfunction "2_2") (pintype "unspecified"))
    )
    (net (code "69") (name "Net-(P8-Pad1)") (class "Default")
      (node (ref "P8") (pin "1") (pinfunction "1_1") (pintype "unspecified"))
      (node (ref "R26") (pin "2") (pinfunction "2_2") (pintype "unspecified"))
    )
    (net (code "70") (name "Net-(P8-Pad4)") (class "Default")
      (node (ref "P8") (pin "4") (pinfunction "4_4") (pintype "unspecified"))
      (node (ref "R22") (pin "1") (pinfunction "1_1") (pintype "unspecified"))
    )
    (net (code "71") (name "Net-(R4-Pad1)") (class "Default")
      (node (ref "R4") (pin "1") (pinfunction "1_1") (pintype "unspecified"))
      (node (ref "R8") (pin "2") (pinfunction "2_2") (pintype "input"))
      (node (ref "R8") (pin "3") (pinfunction "3_3") (pintype "input"))
    )
    (net (code "72") (name "Net-(R14-Pad1)") (class "Default")
      (node (ref "R14") (pin "1") (pinfunction "1_1") (pintype "input"))
      (node (ref "R17") (pin "2") (pinfunction "2_2") (pintype "input"))
    )
    (net (code "73") (name "Net-(R33-Pad1)") (class "Default")
      (node (ref "R33") (pin "1") (pinfunction "1_1") (pintype "unspecified"))
      (node (ref "R35") (pin "1") (pinfunction "1_1") (pintype "unspecified"))
      (node (ref "S2") (pin "1") (pinfunction "1_1") (pintype "input"))
    )
    (net (code "74") (name "Net-(R36-Pad1)") (class "Default")
      (node (ref "R36") (pin "1") (pinfunction "1_1") (pintype "unspecified"))
      (node (ref "R38") (pin "1") (pinfunction "1_1") (pintype "unspecified"))
      (node (ref "S2") (pin "2") (pinfunction "2_2") (pintype "input"))
    )
    (net (code "75") (name "Net-(R39-Pad1)") (class "Default")
      (node (ref "R39") (pin "1") (pinfunction "1_1") (pintype "unspecified"))
      (node (ref "R40") (pin "1") (pinfunction "1_1") (pintype "unspecified"))
      (node (ref "S3") (pin "1") (pinfunction "1_1") (pintype "input"))
    )
    (net (code "76") (name "Net-(R41-Pad1)") (class "Default")
      (node (ref "R41") (pin "1") (pinfunction "1_1") (pintype "unspecified"))
      (node (ref "R42") (pin "1") (pinfunction "1_1") (pintype "unspecified"))
      (node (ref "S4") (pin "1") (pinfunction "1_1") (pintype "input"))
    )
    (net (code "77") (name "Net-(R43-Pad1)") (class "Default")
      (node (ref "R43") (pin "1") (pinfunction "1_1") (pintype "unspecified"))
      (node (ref "R44") (pin "1") (pinfunction "1_1") (pintype "unspecified"))
      (node (ref "S5") (pin "1") (pinfunction "1_1") (pintype "input"))
    )
    (net (code "78") (name "Net-(R49-Pad1)") (class "Default")
      (node (ref "R49") (pin "1") (pinfunction "1_1") (pintype "unspecified"))
      (node (ref "R50") (pin "1") (pinfunction "1_1") (pintype "unspecified"))
      (node (ref "S6") (pin "1") (pinfunction "1_1") (pintype "input"))
    )
    (net (code "79") (name "Net-(R51-Pad1)") (class "Default")
      (node (ref "R51") (pin "1") (pinfunction "1_1") (pintype "unspecified"))
      (node (ref "R52") (pin "1") (pinfunction "1_1") (pintype "unspecified"))
      (node (ref "S7") (pin "1") (pinfunction "1_1") (pintype "input"))
    )
    (net (code "80") (name "Net-(R53-Pad1)") (class "Default")
      (node (ref "R53") (pin "1") (pinfunction "1_1") (pintype "unspecified"))
      (node (ref "R54") (pin "1") (pinfunction "1_1") (pintype "unspecified"))
      (node (ref "S8") (pin "1") (pinfunction "1_1") (pintype "input"))
    )
    (net (code "81") (name "Net-(R122-Pad1)") (class "Default")
      (node (ref "R122") (pin "1") (pinfunction "1_1") (pintype "unspecified"))
      (node (ref "R25") (pin "1") (pinfunction "1_1") (pintype "unspecified"))
      (node (ref "S9") (pin "1") (pinfunction "1_1") (pintype "input"))
    )
    (net (code "82") (name "Net-(R123-Pad1)") (class "Default")
      (node (ref "R123") (pin "1") (pinfunction "1_1") (pintype "unspecified"))
      (node (ref "R24") (pin "1") (pinfunction "1_1") (pintype "unspecified"))
      (node (ref "S9") (pin "2") (pinfunction "2_2") (pintype "input"))
    )
    (net (code "83") (name "Net-(S2-Pad3)") (class "Default")
      (node (ref "S2") (pin "3") (pinfunction "3_3") (pintype "input"))
      (node (ref "S2") (pin "4") (pinfunction "4_4") (pintype "input"))
      (node (ref "S3") (pin "2") (pinfunction "2_2") (pintype "input"))
      (node (ref "S4") (pin "2") (pinfunction "2_2") (pintype "input"))
      (node (ref "S5") (pin "2") (pinfunction "2_2") (pintype "input"))
      (node (ref "S6") (pin "2") (pinfunction "2_2") (pintype "input"))
      (node (ref "S7") (pin "2") (pinfunction "2_2") (pintype "input"))
      (node (ref "S8") (pin "2") (pinfunction "2_2") (pintype "input"))
      (node (ref "S9") (pin "3") (pinfunction "3_3") (pintype "input"))
      (node (ref "S9") (pin "4") (pinfunction "4_4") (pintype "input"))
    )
    (net (code "84") (name "Net-(U4-BOOT)") (class "Default")
      (node (ref "C5") (pin "1") (pinfunction "1_1") (pintype "unspecified"))
      (node (ref "U4") (pin "1") (pinfunction "BOOT_1") (pintype "unspecified"))
    )
    (net (code "85") (name "Net-(U4-COMP)") (class "Default")
      (node (ref "R11") (pin "2") (pinfunction "2_2") (pintype "unspecified"))
      (node (ref "U4") (pin "6") (pinfunction "COMP_6") (pintype "unspecified"))
    )
    (net (code "86") (name "Net-(U4-FB)") (class "Default")
      (node (ref "R10") (pin "2") (pinfunction "2_2") (pintype "unspecified"))
      (node (ref "R8") (pin "1") (pinfunction "1_1") (pintype "input"))
      (node (ref "U4") (pin "5") (pinfunction "FB_5") (pintype "unspecified"))
    )
    (net (code "87") (name "Net-(U4-RT{slash}CLK)") (class "Default")
      (node (ref "R9") (pin "2") (pinfunction "2_2") (pintype "unspecified"))
      (node (ref "U4") (pin "4") (pinfunction "RT/CLK_4") (pintype "unspecified"))
    )
    (net (code "88") (name "Net-(U4-SW)") (class "Default")
      (node (ref "C5") (pin "2") (pinfunction "2_2") (pintype "unspecified"))
      (node (ref "L1") (pin "1") (pinfunction "1_1") (pintype "unspecified"))
      (node (ref "U4") (pin "8") (pinfunction "SW_8") (pintype "unspecified"))
    )
    (net (code "89") (name "Net-(U6-ISET)") (class "Default")
      (node (ref "R18") (pin "2") (pinfunction "2_2") (pintype "unspecified"))
      (node (ref "U6") (pin "3") (pinfunction "ISET_3") (pintype "unspecified"))
    )
    (net (code "90") (name "Net-(U7-BOOT)") (class "Default")
      (node (ref "C16") (pin "1") (pinfunction "1_1") (pintype "unspecified"))
      (node (ref "U7") (pin "1") (pinfunction "BOOT_1") (pintype "unspecified"))
    )
    (net (code "91") (name "Net-(U7-COMP)") (class "Default")
      (node (ref "R21") (pin "2") (pinfunction "2_2") (pintype "unspecified"))
      (node (ref "U7") (pin "6") (pinfunction "COMP_6") (pintype "unspecified"))
    )
    (net (code "92") (name "Net-(U7-FB)") (class "Default")
      (node (ref "R17") (pin "1") (pinfunction "1_1") (pintype "input"))
      (node (ref "R20") (pin "2") (pinfunction "2_2") (pintype "unspecified"))
      (node (ref "U7") (pin "5") (pinfunction "FB_5") (pintype "unspecified"))
    )
    (net (code "93") (name "Net-(U7-RT{slash}CLK)") (class "Default")
      (node (ref "R19") (pin "2") (pinfunction "2_2") (pintype "unspecified"))
      (node (ref "U7") (pin "4") (pinfunction "RT/CLK_4") (pintype "unspecified"))
    )
    (net (code "94") (name "Net-(U7-SW)") (class "Default")
      (node (ref "C16") (pin "2") (pinfunction "2_2") (pintype "unspecified"))
      (node (ref "L2") (pin "1") (pinfunction "1_1") (pintype "unspecified"))
      (node (ref "U7") (pin "8") (pinfunction "SW_8") (pintype "unspecified"))
    )
    (net (code "95") (name "VCC3V3") (class "Default")
      (node (ref "C3") (pin "1") (pinfunction "1_1") (pintype "input"))
      (node (ref "C4") (pin "1") (pinfunction "1_1") (pintype "unspecified"))
      (node (ref "P15") (pin "3") (pinfunction "3_3") (pintype "unspecified"))
      (node (ref "P5") (pin "1") (pinfunction "1_1") (pintype "unspecified"))
      (node (ref "P7") (pin "4") (pinfunction "4_4") (pintype "unspecified"))
      (node (ref "P8") (pin "3") (pinfunction "3_3") (pintype "unspecified"))
      (node (ref "R1") (pin "1") (pinfunction "1_1") (pintype "unspecified"))
      (node (ref "R24") (pin "2") (pinfunction "2_2") (pintype "unspecified"))
      (node (ref "R25") (pin "2") (pinfunction "2_2") (pintype "unspecified"))
      (node (ref "R35") (pin "2") (pinfunction "2_2") (pintype "unspecified"))
      (node (ref "R36") (pin "2") (pinfunction "2_2") (pintype "unspecified"))
      (node (ref "R39") (pin "2") (pinfunction "2_2") (pintype "unspecified"))
      (node (ref "R41") (pin "2") (pinfunction "2_2") (pintype "unspecified"))
      (node (ref "R43") (pin "2") (pinfunction "2_2") (pintype "unspecified"))
      (node (ref "R49") (pin "2") (pinfunction "2_2") (pintype "unspecified"))
      (node (ref "R51") (pin "2") (pinfunction "2_2") (pintype "unspecified"))
      (node (ref "R53") (pin "2") (pinfunction "2_2") (pintype "unspecified"))
      (node (ref "U2") (pin "5") (pinfunction "VOUT_5") (pintype "unspecified"))
    )
    (net (code "96") (name "VCC5V") (class "Default")
      (node (ref "C1") (pin "1") (pinfunction "1_1") (pintype "input"))
      (node (ref "C18") (pin "1") (pinfunction "1_1") (pintype "input"))
      (node (ref "C19") (pin "1") (pinfunction "1_1") (pintype "unspecified"))
      (node (ref "C2") (pin "1") (pinfunction "1_1") (pintype "unspecified"))
      (node (ref "D2") (pin "1") (pinfunction "K_1") (pintype "unspecified"))
      (node (ref "R14") (pin "2") (pinfunction "2_2") (pintype "input"))
      (node (ref "R15") (pin "2") (pinfunction "2_2") (pintype "unspecified"))
      (node (ref "U1") (pin "5") (pinfunction "5V_5") (pintype "unspecified"))
      (node (ref "U1") (pin "6") (pinfunction "5V_6") (pintype "unspecified"))
      (node (ref "U2") (pin "1") (pinfunction "VIN_1") (pintype "unspecified"))
      (node (ref "U5") (pin "1") (pinfunction "VIN_1") (pintype "unspecified"))
      (node (ref "U6") (pin "5") (pinfunction "IN_5") (pintype "unspecified"))
    )
    (net (code "97") (name "VCC5V-EXT") (class "Default")
      (node (ref "C23") (pin "1") (pinfunction "1_1") (pintype "unspecified"))
      (node (ref "P10") (pin "1") (pinfunction "1_1") (pintype "unspecified"))
      (node (ref "P11") (pin "4") (pinfunction "4_4") (pintype "unspecified"))
      (node (ref "P12") (pin "9") (pinfunction "9_9") (pintype "unspecified"))
      (node (ref "P6") (pin "7") (pinfunction "7_7") (pintype "unspecified"))
      (node (ref "R16") (pin "2") (pinfunction "2_2") (pintype "unspecified"))
      (node (ref "U6") (pin "1") (pinfunction "OUT_1") (pintype "unspecified"))
    )
    (net (code "98") (name "VCCBAT") (class "Default")
      (node (ref "C12") (pin "2") (pinfunction "2_2") (pintype "input"))
      (node (ref "C13") (pin "1") (pinfunction "1_1") (pintype "unspecified"))
      (node (ref "C14") (pin "1") (pinfunction "1_1") (pintype "unspecified"))
      (node (ref "D3") (pin "2") (pinfunction "A_2") (pintype "unspecified"))
      (node (ref "DCOUT1") (pin "1") (pinfunction "1_1") (pintype "unspecified"))
      (node (ref "P10") (pin "2") (pinfunction "2_2") (pintype "unspecified"))
      (node (ref "R58") (pin "2") (pinfunction "2_2") (pintype "unspecified"))
      (node (ref "S1") (pin "2") (pinfunction "2_2") (pintype "unspecified"))
      (node (ref "U4") (pin "2") (pinfunction "VIN_2") (pintype "unspecified"))
      (node (ref "U4") (pin "3") (pinfunction "EN_3") (pintype "unspecified"))
    )
    (net (code "99") (name "VCCOP") (class "Default")
      (node (ref "C20") (pin "1") (pinfunction "1_1") (pintype "input"))
      (node (ref "C21") (pin "1") (pinfunction "1_1") (pintype "unspecified"))
      (node (ref "P17") (pin "2") (pinfunction "2_2") (pintype "unspecified"))
      (node (ref "P18") (pin "2") (pinfunction "2_2") (pintype "unspecified"))
      (node (ref "R13") (pin "1") (pinfunction "1_1") (pintype "unspecified"))
      (node (ref "U5") (pin "5") (pinfunction "VOUT_5") (pintype "unspecified"))
    )
    (net (code "100") (name "VCCSreer") (class "Default")
      (node (ref "C6") (pin "2") (pinfunction "2_2") (pintype "unspecified"))
      (node (ref "C7") (pin "1") (pinfunction "1_1") (pintype "input"))
      (node (ref "L1") (pin "2") (pinfunction "2_2") (pintype "unspecified"))
      (node (ref "P3") (pin "2") (pinfunction "2_2") (pintype "unspecified"))
      (node (ref "R4") (pin "2") (pinfunction "2_2") (pintype "unspecified"))
      (node (ref "R5") (pin "2") (pinfunction "2_2") (pintype "unspecified"))
    )
    (net (code "101") (name "unconnected-(P5-Pad7)") (class "Default")
      (node (ref "P5") (pin "7") (pinfunction "7_7") (pintype "unspecified+no_connect"))
    )
    (net (code "102") (name "unconnected-(P5-Pad8)") (class "Default")
      (node (ref "P5") (pin "8") (pinfunction "8_8") (pintype "unspecified+no_connect"))
    )
    (net (code "103") (name "unconnected-(P6-Pad2)") (class "Default")
      (node (ref "P6") (pin "2") (pinfunction "2_2") (pintype "unspecified+no_connect"))
    )
    (net (code "104") (name "unconnected-(P10-Pad6)") (class "Default")
      (node (ref "P10") (pin "6") (pinfunction "6_6") (pintype "unspecified+no_connect"))
    )
    (net (code "105") (name "unconnected-(P12-Pad2)") (class "Default")
      (node (ref "P12") (pin "2") (pinfunction "2_2") (pintype "unspecified+no_connect"))
    )
    (net (code "106") (name "unconnected-(S1-Pad3)") (class "Default")
      (node (ref "S1") (pin "3") (pinfunction "3_3") (pintype "unspecified+no_connect"))
    )
    (net (code "107") (name "unconnected-(U1-0.0-Pad9)") (class "Default")
      (node (ref "U1") (pin "9") (pinfunction "0.0_9") (pintype "unspecified+no_connect"))
    )
    (net (code "108") (name "unconnected-(U1-0.1-Pad10)") (class "Default")
      (node (ref "U1") (pin "10") (pinfunction "0.1_10") (pintype "unspecified+no_connect"))
    )
    (net (code "109") (name "unconnected-(U1-0.2-Pad11)") (class "Default")
      (node (ref "U1") (pin "11") (pinfunction "0.2_11") (pintype "unspecified"))
    )
    (net (code "110") (name "unconnected-(U1-0.3-Pad12)") (class "Default")
      (node (ref "U1") (pin "12") (pinfunction "0.3_12") (pintype "unspecified"))
    )
    (net (code "111") (name "unconnected-(U1-1.0-Pad13)") (class "Default")
      (node (ref "U1") (pin "13") (pinfunction "1.0_13") (pintype "unspecified"))
    )
    (net (code "112") (name "unconnected-(U1-3.0-Pad20)") (class "Default")
      (node (ref "U1") (pin "20") (pinfunction "3.0_20") (pintype "unspecified"))
    )
    (net (code "113") (name "unconnected-(U1-3.1-Pad21)") (class "Default")
      (node (ref "U1") (pin "21") (pinfunction "3.1_21") (pintype "unspecified"))
    )
    (net (code "114") (name "unconnected-(U1-3.2-Pad22)") (class "Default")
      (node (ref "U1") (pin "22") (pinfunction "3.2_22") (pintype "unspecified"))
    )
    (net (code "115") (name "unconnected-(U1-3.3-Pad23)") (class "Default")
      (node (ref "U1") (pin "23") (pinfunction "3.3_23") (pintype "unspecified"))
    )
    (net (code "116") (name "unconnected-(U1-3.4-Pad24)") (class "Default")
      (node (ref "U1") (pin "24") (pinfunction "3.4_24") (pintype "unspecified"))
    )
    (net (code "117") (name "unconnected-(U1-3V3-Pad3)") (class "Default")
      (node (ref "U1") (pin "3") (pinfunction "3V3_3") (pintype "unspecified+no_connect"))
    )
    (net (code "118") (name "unconnected-(U1-3V3-Pad4)") (class "Default")
      (node (ref "U1") (pin "4") (pinfunction "3V3_4") (pintype "unspecified+no_connect"))
    )
    (net (code "119") (name "unconnected-(U1-5.0-Pad27)") (class "Default")
      (node (ref "U1") (pin "27") (pinfunction "5.0_27") (pintype "unspecified"))
    )
    (net (code "120") (name "unconnected-(U1-5.1-Pad28)") (class "Default")
      (node (ref "U1") (pin "28") (pinfunction "5.1_28") (pintype "unspecified"))
    )
    (net (code "121") (name "unconnected-(U1-5.2-Pad29)") (class "Default")
      (node (ref "U1") (pin "29") (pinfunction "5.2_29") (pintype "unspecified"))
    )
    (net (code "122") (name "unconnected-(U1-5.3-Pad30)") (class "Default")
      (node (ref "U1") (pin "30") (pinfunction "5.3_30") (pintype "unspecified"))
    )
    (net (code "123") (name "unconnected-(U1-5.4-Pad31)") (class "Default")
      (node (ref "U1") (pin "31") (pinfunction "5.4_31") (pintype "unspecified"))
    )
    (net (code "124") (name "unconnected-(U1-6.2-Pad34)") (class "Default")
      (node (ref "U1") (pin "34") (pinfunction "6.2_34") (pintype "unspecified"))
    )
    (net (code "125") (name "unconnected-(U1-6.3-Pad35)") (class "Default")
      (node (ref "U1") (pin "35") (pinfunction "6.3_35") (pintype "unspecified"))
    )
    (net (code "126") (name "unconnected-(U1-6.4-Pad36)") (class "Default")
      (node (ref "U1") (pin "36") (pinfunction "6.4_36") (pintype "unspecified"))
    )
    (net (code "127") (name "unconnected-(U1-6.5-Pad37)") (class "Default")
      (node (ref "U1") (pin "37") (pinfunction "6.5_37") (pintype "unspecified"))
    )
    (net (code "128") (name "unconnected-(U1-6.6-Pad38)") (class "Default")
      (node (ref "U1") (pin "38") (pinfunction "6.6_38") (pintype "unspecified"))
    )
    (net (code "129") (name "unconnected-(U1-6.7-Pad39)") (class "Default")
      (node (ref "U1") (pin "39") (pinfunction "6.7_39") (pintype "unspecified"))
    )
    (net (code "130") (name "unconnected-(U1-7.0-Pad40)") (class "Default")
      (node (ref "U1") (pin "40") (pinfunction "7.0_40") (pintype "unspecified"))
    )
    (net (code "131") (name "unconnected-(U1-7.1-Pad41)") (class "Default")
      (node (ref "U1") (pin "41") (pinfunction "7.1_41") (pintype "unspecified"))
    )
    (net (code "132") (name "unconnected-(U1-7.2-Pad42)") (class "Default")
      (node (ref "U1") (pin "42") (pinfunction "7.2_42") (pintype "unspecified"))
    )
    (net (code "133") (name "unconnected-(U1-7.3-Pad43)") (class "Default")
      (node (ref "U1") (pin "43") (pinfunction "7.3_43") (pintype "unspecified"))
    )
    (net (code "134") (name "unconnected-(U1-7.4-Pad44)") (class "Default")
      (node (ref "U1") (pin "44") (pinfunction "7.4_44") (pintype "unspecified"))
    )
    (net (code "135") (name "unconnected-(U1-8.0-Pad48)") (class "Default")
      (node (ref "U1") (pin "48") (pinfunction "8.0_48") (pintype "unspecified"))
    )
    (net (code "136") (name "unconnected-(U1-8.1-Pad49)") (class "Default")
      (node (ref "U1") (pin "49") (pinfunction "8.1_49") (pintype "unspecified"))
    )
    (net (code "137") (name "unconnected-(U1-8.2-Pad50)") (class "Default")
      (node (ref "U1") (pin "50") (pinfunction "8.2_50") (pintype "unspecified"))
    )
    (net (code "138") (name "unconnected-(U1-8.3-Pad51)") (class "Default")
      (node (ref "U1") (pin "51") (pinfunction "8.3_51") (pintype "unspecified"))
    )
    (net (code "139") (name "unconnected-(U1-9.1-Pad53)") (class "Default")
      (node (ref "U1") (pin "53") (pinfunction "9.1_53") (pintype "unspecified"))
    )
    (net (code "140") (name "unconnected-(U1-10.3-Pad57)") (class "Default")
      (node (ref "U1") (pin "57") (pinfunction "10.3_57") (pintype "unspecified"))
    )
    (net (code "141") (name "unconnected-(U1-11.1-Pad60)") (class "Default")
      (node (ref "U1") (pin "60") (pinfunction "11.1_60") (pintype "unspecified"))
    )
    (net (code "142") (name "unconnected-(U1-11.2-Pad61)") (class "Default")
      (node (ref "U1") (pin "61") (pinfunction "11.2_61") (pintype "unspecified"))
    )
    (net (code "143") (name "unconnected-(U1-14.1-Pad77)") (class "Default")
      (node (ref "U1") (pin "77") (pinfunction "14.1_77") (pintype "unspecified"))
    )
    (net (code "144") (name "unconnected-(U1-17.0-Pad84)") (class "Default")
      (node (ref "U1") (pin "84") (pinfunction "17.0_84") (pintype "unspecified"))
    )
    (net (code "145") (name "unconnected-(U1-17.1-Pad85)") (class "Default")
      (node (ref "U1") (pin "85") (pinfunction "17.1_85") (pintype "unspecified"))
    )
    (net (code "146") (name "unconnected-(U1-17.2-Pad86)") (class "Default")
      (node (ref "U1") (pin "86") (pinfunction "17.2_86") (pintype "unspecified"))
    )
    (net (code "147") (name "unconnected-(U1-17.3-Pad87)") (class "Default")
      (node (ref "U1") (pin "87") (pinfunction "17.3_87") (pintype "unspecified"))
    )
    (net (code "148") (name "unconnected-(U1-17.4-Pad88)") (class "Default")
      (node (ref "U1") (pin "88") (pinfunction "17.4_88") (pintype "unspecified"))
    )
    (net (code "149") (name "unconnected-(U1-18.0-Pad89)") (class "Default")
      (node (ref "U1") (pin "89") (pinfunction "18.0_89") (pintype "unspecified"))
    )
    (net (code "150") (name "unconnected-(U1-18.1-Pad90)") (class "Default")
      (node (ref "U1") (pin "90") (pinfunction "18.1_90") (pintype "unspecified"))
    )
    (net (code "151") (name "unconnected-(U1-18.2-Pad91)") (class "Default")
      (node (ref "U1") (pin "91") (pinfunction "18.2_91") (pintype "unspecified"))
    )
    (net (code "152") (name "unconnected-(U1-18.3-Pad92)") (class "Default")
      (node (ref "U1") (pin "92") (pinfunction "18.3_92") (pintype "unspecified"))
    )
    (net (code "153") (name "unconnected-(U1-18.4-Pad93)") (class "Default")
      (node (ref "U1") (pin "93") (pinfunction "18.4_93") (pintype "unspecified"))
    )
    (net (code "154") (name "unconnected-(U1-18.5-Pad94)") (class "Default")
      (node (ref "U1") (pin "94") (pinfunction "18.5_94") (pintype "unspecified"))
    )
    (net (code "155") (name "unconnected-(U1-18.6-Pad95)") (class "Default")
      (node (ref "U1") (pin "95") (pinfunction "18.6_95") (pintype "unspecified"))
    )
    (net (code "156") (name "unconnected-(U1-18.7-Pad96)") (class "Default")
      (node (ref "U1") (pin "96") (pinfunction "18.7_96") (pintype "unspecified"))
    )
    (net (code "157") (name "unconnected-(U1-19.2-Pad99)") (class "Default")
      (node (ref "U1") (pin "99") (pinfunction "19.2_99") (pintype "unspecified"))
    )
    (net (code "158") (name "unconnected-(U1-23.1-Pad113)") (class "Default")
      (node (ref "U1") (pin "113") (pinfunction "23.1_113") (pintype "unspecified"))
    )
    (net (code "159") (name "unconnected-(U1-23.3-Pad114)") (class "Default")
      (node (ref "U1") (pin "114") (pinfunction "23.3_114") (pintype "unspecified"))
    )
    (net (code "160") (name "unconnected-(U1-23.4-Pad115)") (class "Default")
      (node (ref "U1") (pin "115") (pinfunction "23.4_115") (pintype "unspecified+no_connect"))
    )
    (net (code "161") (name "unconnected-(U1-23.7-Pad116)") (class "Default")
      (node (ref "U1") (pin "116") (pinfunction "23.7_116") (pintype "unspecified+no_connect"))
    )
    (net (code "162") (name "unconnected-(U2-NC-Pad4)") (class "Default")
      (node (ref "U2") (pin "4") (pinfunction "NC_4") (pintype "unspecified+no_connect"))
    )
    (net (code "163") (name "unconnected-(U5-NC-Pad4)") (class "Default")
      (node (ref "U5") (pin "4") (pinfunction "NC_4") (pintype "unspecified+no_connect"))
    )
  )
)
